# Micro_Controller.net
KiCad netlist of a schematic drawn in Altium Designer
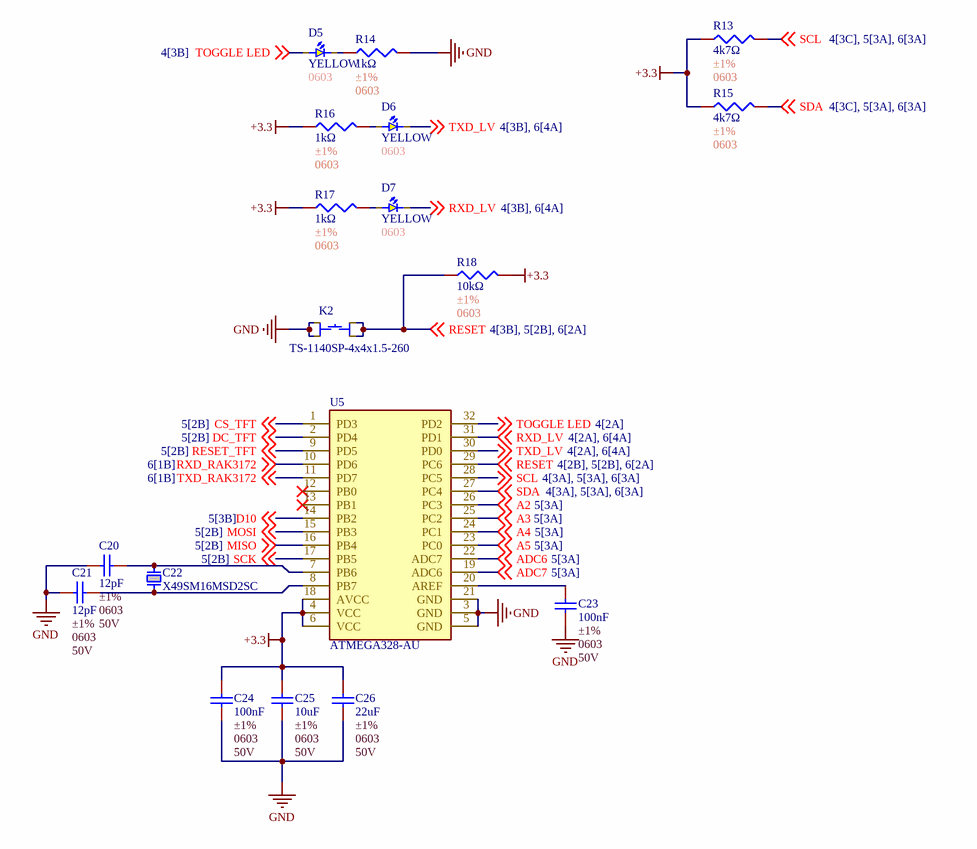
[diagram p0: Micro Controller.SchDoc]

(export (version "E")
  (design (tool "Eeschema 10.0.6"))
  (components
    (comp (ref "C20")
      (value "12pF")
      (footprint "C0603")
      (description "50V 10pF NP0 ±1% 0402 Multilayer Ceramic Capacitors MLCC - SMD/SMT ROHS")
      (fields
        (field (name "MANUFACTURER") "YAGEO")
        (field (name "MFR. PART #") "CC0402FRNPO9BN100")
        (field (name "TOLERANCE") "±1%")
        (field (name "PACKAGE") "0603")
        (field (name "VOLTAGE RATING") "50V")
      )
      (libsource (lib "Capital") (part "C0603_12pF_±1%"))
    )
    (comp (ref "C21")
      (value "12pF")
      (footprint "C0603")
      (description "50V 10pF NP0 ±1% 0402 Multilayer Ceramic Capacitors MLCC - SMD/SMT ROHS")
      (fields
        (field (name "MANUFACTURER") "YAGEO")
        (field (name "MFR. PART #") "CC0402FRNPO9BN100")
        (field (name "TOLERANCE") "±1%")
        (field (name "PACKAGE") "0603")
        (field (name "VOLTAGE RATING") "50V")
      )
      (libsource (lib "Capital") (part "C0603_12pF_±1%"))
    )
    (comp (ref "C22")
      (value "X49SM16MSD2SC")
      (footprint "X49SM16MSD2SC")
      (description "16MHz Crystal Oscillator 20pF ±20ppm ±30ppm HC-49S-SMD Crystals ROHS")
      (fields (field (name "MANUFACTURER") "YXC Crystal Oscillators") (field (name "LCSC PART #") "C12676"))
      (libsource (lib "Oscillator") (part "X49SM16MSD2SC"))
    )
    (comp (ref "C23")
      (value "100nF")
      (footprint "C0603")
      (description "50V 10pF NP0 ±1% 0402 Multilayer Ceramic Capacitors MLCC - SMD/SMT ROHS")
      (fields
        (field (name "MANUFACTURER") "YAGEO")
        (field (name "MFR. PART #") "CC0402FRNPO9BN100")
        (field (name "TOLERANCE") "±1%")
        (field (name "PACKAGE") "0603")
        (field (name "VOLTAGE RATING") "50V")
      )
      (libsource (lib "Capital") (part "C0603_100nF_±1%"))
    )
    (comp (ref "C24")
      (value "100nF")
      (footprint "C0603")
      (description "50V 10pF NP0 ±1% 0402 Multilayer Ceramic Capacitors MLCC - SMD/SMT ROHS")
      (fields
        (field (name "MANUFACTURER") "YAGEO")
        (field (name "MFR. PART #") "CC0402FRNPO9BN100")
        (field (name "TOLERANCE") "±1%")
        (field (name "PACKAGE") "0603")
        (field (name "VOLTAGE RATING") "50V")
      )
      (libsource (lib "Capital") (part "C0603_100nF_±1%"))
    )
    (comp (ref "C25")
      (value "10uF")
      (footprint "C0603")
      (description "50V 10pF NP0 ±1% 0402 Multilayer Ceramic Capacitors MLCC - SMD/SMT ROHS")
      (fields
        (field (name "MANUFACTURER") "YAGEO")
        (field (name "MFR. PART #") "CC0402FRNPO9BN100")
        (field (name "TOLERANCE") "±1%")
        (field (name "PACKAGE") "0603")
        (field (name "VOLTAGE RATING") "50V")
      )
      (libsource (lib "Capital") (part "C0603_10uF_±1%"))
    )
    (comp (ref "C26")
      (value "22uF")
      (footprint "C0603")
      (description "50V 10pF NP0 ±1% 0402 Multilayer Ceramic Capacitors MLCC - SMD/SMT ROHS")
      (fields
        (field (name "MANUFACTURER") "YAGEO")
        (field (name "MFR. PART #") "CC0402FRNPO9BN100")
        (field (name "TOLERANCE") "±1%")
        (field (name "PACKAGE") "0603")
        (field (name "VOLTAGE RATING") "50V")
      )
      (libsource (lib "Capital") (part "C0603_22uF_±1%"))
    )
    (comp (ref "D5")
      (value "YELLOW")
      (footprint "LED0603")
      (description "25mcd~40mcd Water Clear -40℃~+85℃ 624nm Red 120° 60mW 0402 LED Indication - Discrete ROHS")
      (fields
        (field (name "MANUFACTURER") "XINGLIGHT")
        (field (name "MFR. PART #") "XL-1005UGC")
        (field (name "PACKAGE") "0603")
      )
      (libsource (lib "LED") (part "D0603_YELLOW"))
    )
    (comp (ref "D6")
      (value "YELLOW")
      (footprint "LED0603")
      (description "25mcd~40mcd Water Clear -40℃~+85℃ 624nm Red 120° 60mW 0402 LED Indication - Discrete ROHS")
      (fields
        (field (name "MANUFACTURER") "XINGLIGHT")
        (field (name "MFR. PART #") "XL-1005UGC")
        (field (name "PACKAGE") "0603")
      )
      (libsource (lib "LED") (part "D0603_YELLOW"))
    )
    (comp (ref "D7")
      (value "YELLOW")
      (footprint "LED0603")
      (description "25mcd~40mcd Water Clear -40℃~+85℃ 624nm Red 120° 60mW 0402 LED Indication - Discrete ROHS")
      (fields
        (field (name "MANUFACTURER") "XINGLIGHT")
        (field (name "MFR. PART #") "XL-1005UGC")
        (field (name "PACKAGE") "0603")
      )
      (libsource (lib "LED") (part "D0603_YELLOW"))
    )
    (comp (ref "K2")
      (value "TS-1140SP-4x4x1.5-260")
      (footprint "4x4x1.5")
      (description "SMD Tactile Switches ROHS")
      (fields (field (name "MANUFACTURER") "CAX") (field (name "LCSC PART #") "C49023394"))
      (libsource (lib "Switch") (part "TS-1140SP-4x4x1.5-260"))
    )
    (comp (ref "R13")
      (value "4k7Ω")
      (footprint "R0603")
      (description "62.5mW Thick Film Resistor 50V ±1% ±200ppm/℃ 10Ω 0402 Chip Resistor - Surface Mount ROHS")
      (fields
        (field (name "MANUFACTURER") "YAGEO")
        (field (name "MFR. PART #") "RC0402FR-0710RL")
        (field (name "TOLERANCE") "±1%")
        (field (name "PACKAGE") "0603")
      )
      (libsource (lib "Resistor") (part "R0603_4k7Ω_±1%"))
    )
    (comp (ref "R14")
      (value "1kΩ")
      (footprint "R0603")
      (description "62.5mW Thick Film Resistor 50V ±1% ±200ppm/℃ 10Ω 0402 Chip Resistor - Surface Mount ROHS")
      (fields
        (field (name "MANUFACTURER") "YAGEO")
        (field (name "MFR. PART #") "RC0402FR-0710RL")
        (field (name "TOLERANCE") "±1%")
        (field (name "PACKAGE") "0603")
      )
      (libsource (lib "Resistor") (part "R0603_1kΩ_±1%"))
    )
    (comp (ref "R15")
      (value "4k7Ω")
      (footprint "R0603")
      (description "62.5mW Thick Film Resistor 50V ±1% ±200ppm/℃ 10Ω 0402 Chip Resistor - Surface Mount ROHS")
      (fields
        (field (name "MANUFACTURER") "YAGEO")
        (field (name "MFR. PART #") "RC0402FR-0710RL")
        (field (name "TOLERANCE") "±1%")
        (field (name "PACKAGE") "0603")
      )
      (libsource (lib "Resistor") (part "R0603_4k7Ω_±1%"))
    )
    (comp (ref "R16")
      (value "1kΩ")
      (footprint "R0603")
      (description "62.5mW Thick Film Resistor 50V ±1% ±200ppm/℃ 10Ω 0402 Chip Resistor - Surface Mount ROHS")
      (fields
        (field (name "MANUFACTURER") "YAGEO")
        (field (name "MFR. PART #") "RC0402FR-0710RL")
        (field (name "TOLERANCE") "±1%")
        (field (name "PACKAGE") "0603")
      )
      (libsource (lib "Resistor") (part "R0603_1kΩ_±1%"))
    )
    (comp (ref "R17")
      (value "1kΩ")
      (footprint "R0603")
      (description "62.5mW Thick Film Resistor 50V ±1% ±200ppm/℃ 10Ω 0402 Chip Resistor - Surface Mount ROHS")
      (fields
        (field (name "MANUFACTURER") "YAGEO")
        (field (name "MFR. PART #") "RC0402FR-0710RL")
        (field (name "TOLERANCE") "±1%")
        (field (name "PACKAGE") "0603")
      )
      (libsource (lib "Resistor") (part "R0603_1kΩ_±1%"))
    )
    (comp (ref "R18")
      (value "10kΩ")
      (footprint "R0603")
      (description "62.5mW Thick Film Resistor 50V ±1% ±200ppm/℃ 10Ω 0402 Chip Resistor - Surface Mount ROHS")
      (fields
        (field (name "MANUFACTURER") "YAGEO")
        (field (name "MFR. PART #") "RC0402FR-0710RL")
        (field (name "TOLERANCE") "±1%")
        (field (name "PACKAGE") "0603")
      )
      (libsource (lib "Resistor") (part "R0603_10kΩ_±1%"))
    )
    (comp (ref "U5")
      (value "ATMEGA328-AU")
      (footprint "ATMEGA328-AU")
      (description "AVR 20MHz TQFP-32(7x7) Microcontrollers (MCU/MPU/SOC) ROHS")
      (fields (field (name "MANUFACTURER") "MICROCHIP") (field (name "LCSC PART #") "C618731"))
      (libsource (lib "MCU") (part "ATMEGA328-AU"))
    )
  )
  (nets
    (net (code "1") (name "+3.3") (class "Default")
      (node (ref "C24") (pin "1") (pinfunction "1_1") (pintype "passive"))
      (node (ref "C25") (pin "1") (pinfunction "1_1") (pintype "passive"))
      (node (ref "C26") (pin "1") (pinfunction "1_1") (pintype "passive"))
      (node (ref "R13") (pin "1") (pinfunction "1_1") (pintype "passive"))
      (node (ref "R15") (pin "1") (pinfunction "1_1") (pintype "passive"))
      (node (ref "R16") (pin "1") (pinfunction "1_1") (pintype "passive"))
      (node (ref "R17") (pin "1") (pinfunction "1_1") (pintype "passive"))
      (node (ref "R18") (pin "2") (pinfunction "2_2") (pintype "passive"))
      (node (ref "U5") (pin "18") (pinfunction "AVCC_18") (pintype "passive"))
      (node (ref "U5") (pin "4") (pinfunction "VCC_4") (pintype "passive"))
      (node (ref "U5") (pin "6") (pinfunction "VCC_6") (pintype "passive"))
    )
    (net (code "2") (name "A2") (class "Default")
      (node (ref "U5") (pin "26") (pinfunction "PC3_26") (pintype "passive"))
    )
    (net (code "3") (name "A3") (class "Default")
      (node (ref "U5") (pin "25") (pinfunction "PC2_25") (pintype "passive"))
    )
    (net (code "4") (name "A4") (class "Default")
      (node (ref "U5") (pin "24") (pinfunction "PC1_24") (pintype "passive"))
    )
    (net (code "5") (name "A5") (class "Default")
      (node (ref "U5") (pin "23") (pinfunction "PC0_23") (pintype "passive"))
    )
    (net (code "6") (name "ADC6") (class "Default")
      (node (ref "U5") (pin "22") (pinfunction "ADC7_22") (pintype "passive"))
    )
    (net (code "7") (name "ADC7") (class "Default")
      (node (ref "U5") (pin "19") (pinfunction "ADC6_19") (pintype "passive"))
    )
    (net (code "8") (name "CS_TFT") (class "Default")
      (node (ref "U5") (pin "1") (pinfunction "PD3_1") (pintype "passive"))
    )
    (net (code "9") (name "D10") (class "Default")
      (node (ref "U5") (pin "14") (pinfunction "PB2_14") (pintype "passive"))
    )
    (net (code "10") (name "DC_TFT") (class "Default")
      (node (ref "U5") (pin "2") (pinfunction "PD4_2") (pintype "passive"))
    )
    (net (code "11") (name "GND") (class "Default")
      (node (ref "C20") (pin "2") (pinfunction "2_2") (pintype "passive"))
      (node (ref "C21") (pin "2") (pinfunction "2_2") (pintype "passive"))
      (node (ref "C23") (pin "2") (pinfunction "2_2") (pintype "passive"))
      (node (ref "C24") (pin "2") (pinfunction "2_2") (pintype "passive"))
      (node (ref "C25") (pin "2") (pinfunction "2_2") (pintype "passive"))
      (node (ref "C26") (pin "2") (pinfunction "2_2") (pintype "passive"))
      (node (ref "K2") (pin "1") (pinfunction "1_1") (pintype "passive"))
      (node (ref "K2") (pin "3") (pinfunction "3_3") (pintype "passive"))
      (node (ref "R14") (pin "2") (pinfunction "2_2") (pintype "passive"))
      (node (ref "U5") (pin "21") (pinfunction "GND_21") (pintype "passive"))
      (node (ref "U5") (pin "3") (pinfunction "GND_3") (pintype "passive"))
      (node (ref "U5") (pin "5") (pinfunction "GND_5") (pintype "passive"))
    )
    (net (code "12") (name "MISO") (class "Default")
      (node (ref "U5") (pin "16") (pinfunction "PB4_16") (pintype "passive"))
    )
    (net (code "13") (name "MOSI") (class "Default")
      (node (ref "U5") (pin "15") (pinfunction "PB3_15") (pintype "passive"))
    )
    (net (code "14") (name "Net-(D5-Pad1)") (class "Default")
      (node (ref "D5") (pin "1") (pinfunction "1_1") (pintype "passive"))
      (node (ref "R14") (pin "1") (pinfunction "1_1") (pintype "passive"))
    )
    (net (code "15") (name "Net-(D6-Pad2)") (class "Default")
      (node (ref "D6") (pin "2") (pinfunction "2_2") (pintype "passive"))
      (node (ref "R16") (pin "2") (pinfunction "2_2") (pintype "passive"))
    )
    (net (code "16") (name "Net-(D7-Pad2)") (class "Default")
      (node (ref "D7") (pin "2") (pinfunction "2_2") (pintype "passive"))
      (node (ref "R17") (pin "2") (pinfunction "2_2") (pintype "passive"))
    )
    (net (code "17") (name "Net-(U5-AREF)") (class "Default")
      (node (ref "C23") (pin "1") (pinfunction "1_1") (pintype "passive"))
      (node (ref "U5") (pin "20") (pinfunction "AREF_20") (pintype "passive"))
    )
    (net (code "18") (name "Net-(U5-PB6)") (class "Default")
      (node (ref "C20") (pin "1") (pinfunction "1_1") (pintype "passive"))
      (node (ref "C22") (pin "2") (pinfunction "2_2") (pintype "passive"))
      (node (ref "U5") (pin "7") (pinfunction "PB6_7") (pintype "passive"))
    )
    (net (code "19") (name "Net-(U5-PB7)") (class "Default")
      (node (ref "C21") (pin "1") (pinfunction "1_1") (pintype "passive"))
      (node (ref "C22") (pin "1") (pinfunction "1_1") (pintype "passive"))
      (node (ref "U5") (pin "8") (pinfunction "PB7_8") (pintype "passive"))
    )
    (net (code "20") (name "RESET") (class "Default")
      (node (ref "K2") (pin "2") (pinfunction "2_2") (pintype "passive"))
      (node (ref "K2") (pin "4") (pinfunction "4_4") (pintype "passive"))
      (node (ref "R18") (pin "1") (pinfunction "1_1") (pintype "passive"))
      (node (ref "U5") (pin "29") (pinfunction "PC6_29") (pintype "passive"))
    )
    (net (code "21") (name "RESET_TFT") (class "Default")
      (node (ref "U5") (pin "9") (pinfunction "PD5_9") (pintype "passive"))
    )
    (net (code "22") (name "RXD_LV") (class "Default")
      (node (ref "D7") (pin "1") (pinfunction "1_1") (pintype "passive"))
      (node (ref "U5") (pin "31") (pinfunction "PD1_31") (pintype "passive"))
    )
    (net (code "23") (name "RXD_RAK3172") (class "Default")
      (node (ref "U5") (pin "10") (pinfunction "PD6_10") (pintype "passive"))
    )
    (net (code "24") (name "SCK") (class "Default")
      (node (ref "U5") (pin "17") (pinfunction "PB5_17") (pintype "passive"))
    )
    (net (code "25") (name "SCL") (class "Default")
      (node (ref "R13") (pin "2") (pinfunction "2_2") (pintype "passive"))
      (node (ref "U5") (pin "28") (pinfunction "PC5_28") (pintype "passive"))
    )
    (net (code "26") (name "SDA") (class "Default")
      (node (ref "R15") (pin "2") (pinfunction "2_2") (pintype "passive"))
      (node (ref "U5") (pin "27") (pinfunction "PC4_27") (pintype "passive"))
    )
    (net (code "27") (name "TOGGLE LED") (class "Default")
      (node (ref "D5") (pin "2") (pinfunction "2_2") (pintype "passive"))
      (node (ref "U5") (pin "32") (pinfunction "PD2_32") (pintype "passive"))
    )
    (net (code "28") (name "TXD_LV") (class "Default")
      (node (ref "D6") (pin "1") (pinfunction "1_1") (pintype "passive"))
      (node (ref "U5") (pin "30") (pinfunction "PD0_30") (pintype "passive"))
    )
    (net (code "29") (name "TXD_RAK3172") (class "Default")
      (node (ref "U5") (pin "11") (pinfunction "PD7_11") (pintype "passive"))
    )
    (net (code "30") (name "unconnected-(U5-PB0-Pad12)") (class "Default")
      (node (ref "U5") (pin "12") (pinfunction "PB0_12") (pintype "passive+no_connect"))
    )
    (net (code "31") (name "unconnected-(U5-PB1-Pad13)") (class "Default")
      (node (ref "U5") (pin "13") (pinfunction "PB1_13") (pintype "passive+no_connect"))
    )
  )
)
